# Analog_Breakout_-_Schematic.net
KiCad netlist of a schematic drawn in EAGLE
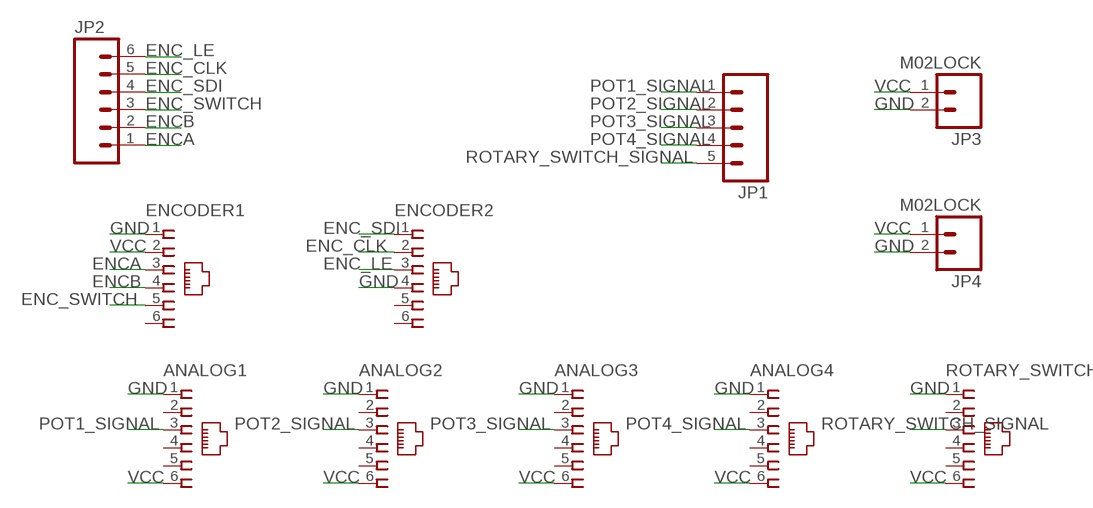
[diagram p0: schematic, sheet 1]

(export (version "E")
  (design (tool "Eeschema 10.0.6"))
  (components
    (comp (ref "ANALOG1")
      (value "555165-1")
      (footprint "eagle-import:555165-1")
      (libsource (lib "eagle-import") (part "555165-1"))
    )
    (comp (ref "ANALOG2")
      (value "555165-1")
      (footprint "eagle-import:555165-1")
      (libsource (lib "eagle-import") (part "555165-1"))
    )
    (comp (ref "ANALOG3")
      (value "555165-1")
      (footprint "eagle-import:555165-1")
      (libsource (lib "eagle-import") (part "555165-1"))
    )
    (comp (ref "ANALOG4")
      (value "555165-1")
      (footprint "eagle-import:555165-1")
      (libsource (lib "eagle-import") (part "555165-1"))
    )
    (comp (ref "ENCODER1")
      (value "555165-1")
      (footprint "eagle-import:555165-1")
      (libsource (lib "eagle-import") (part "555165-1"))
    )
    (comp (ref "ENCODER2")
      (value "555165-1")
      (footprint "eagle-import:555165-1")
      (libsource (lib "eagle-import") (part "555165-1"))
    )
    (comp (ref "JP1")
      (value "M05LOCK")
      (footprint "eagle-import:1X05_LOCK")
      (libsource (lib "eagle-import") (part "M05LOCK"))
    )
    (comp (ref "JP2")
      (value "M06LOCK")
      (footprint "eagle-import:1X06_LOCK")
      (libsource (lib "eagle-import") (part "M06LOCK"))
    )
    (comp (ref "JP3")
      (value "M02LOCK")
      (footprint "eagle-import:1X02_LOCK")
      (libsource (lib "eagle-import") (part "M02LOCK"))
    )
    (comp (ref "JP4")
      (value "M02LOCK")
      (footprint "eagle-import:1X02_LOCK")
      (libsource (lib "eagle-import") (part "M02LOCK"))
    )
    (comp (ref "ROTARY_SWITCH")
      (value "555165-1")
      (footprint "eagle-import:555165-1")
      (libsource (lib "eagle-import") (part "555165-1"))
    )
  )
  (nets
    (net (code "1") (name "/ENCA") (class "Default")
      (node (ref "ENCODER1") (pin "3") (pinfunction "3_3") (pintype "passive"))
      (node (ref "JP2") (pin "1") (pinfunction "1_1") (pintype "passive"))
    )
    (net (code "2") (name "/ENCB") (class "Default")
      (node (ref "ENCODER1") (pin "4") (pinfunction "4_4") (pintype "passive"))
      (node (ref "JP2") (pin "2") (pinfunction "2_2") (pintype "passive"))
    )
    (net (code "3") (name "/ENC_CLK") (class "Default")
      (node (ref "ENCODER2") (pin "2") (pinfunction "2_2") (pintype "passive"))
      (node (ref "JP2") (pin "5") (pinfunction "5_5") (pintype "passive"))
    )
    (net (code "4") (name "/ENC_LE") (class "Default")
      (node (ref "ENCODER2") (pin "3") (pinfunction "3_3") (pintype "passive"))
      (node (ref "JP2") (pin "6") (pinfunction "6_6") (pintype "passive"))
    )
    (net (code "5") (name "/ENC_SDI") (class "Default")
      (node (ref "ENCODER2") (pin "1") (pinfunction "1_1") (pintype "passive"))
      (node (ref "JP2") (pin "4") (pinfunction "4_4") (pintype "passive"))
    )
    (net (code "6") (name "/ENC_SWITCH") (class "Default")
      (node (ref "ENCODER1") (pin "5") (pinfunction "5_5") (pintype "passive"))
      (node (ref "JP2") (pin "3") (pinfunction "3_3") (pintype "passive"))
    )
    (net (code "7") (name "/GND") (class "Default")
      (node (ref "ANALOG1") (pin "1") (pinfunction "1_1") (pintype "passive"))
      (node (ref "ANALOG2") (pin "1") (pinfunction "1_1") (pintype "passive"))
      (node (ref "ANALOG3") (pin "1") (pinfunction "1_1") (pintype "passive"))
      (node (ref "ANALOG4") (pin "1") (pinfunction "1_1") (pintype "passive"))
      (node (ref "ENCODER1") (pin "1") (pinfunction "1_1") (pintype "passive"))
      (node (ref "ENCODER2") (pin "4") (pinfunction "4_4") (pintype "passive"))
      (node (ref "JP3") (pin "2") (pinfunction "2_2") (pintype "passive"))
      (node (ref "JP4") (pin "2") (pinfunction "2_2") (pintype "passive"))
      (node (ref "ROTARY_SWITCH") (pin "1") (pinfunction "1_1") (pintype "passive"))
    )
    (net (code "8") (name "/POT1_SIGNAL") (class "Default")
      (node (ref "ANALOG1") (pin "3") (pinfunction "3_3") (pintype "passive"))
      (node (ref "JP1") (pin "1") (pinfunction "1_1") (pintype "passive"))
    )
    (net (code "9") (name "/POT2_SIGNAL") (class "Default")
      (node (ref "ANALOG2") (pin "3") (pinfunction "3_3") (pintype "passive"))
      (node (ref "JP1") (pin "2") (pinfunction "2_2") (pintype "passive"))
    )
    (net (code "10") (name "/POT3_SIGNAL") (class "Default")
      (node (ref "ANALOG3") (pin "3") (pinfunction "3_3") (pintype "passive"))
      (node (ref "JP1") (pin "3") (pinfunction "3_3") (pintype "passive"))
    )
    (net (code "11") (name "/POT4_SIGNAL") (class "Default")
      (node (ref "ANALOG4") (pin "3") (pinfunction "3_3") (pintype "passive"))
      (node (ref "JP1") (pin "4") (pinfunction "4_4") (pintype "passive"))
    )
    (net (code "12") (name "/ROTARY_SWITCH_SIGNAL") (class "Default")
      (node (ref "JP1") (pin "5") (pinfunction "5_5") (pintype "passive"))
      (node (ref "ROTARY_SWITCH") (pin "3") (pinfunction "3_3") (pintype "passive"))
    )
    (net (code "13") (name "/VCC") (class "Default")
      (node (ref "ANALOG1") (pin "6") (pinfunction "6_6") (pintype "passive"))
      (node (ref "ANALOG2") (pin "6") (pinfunction "6_6") (pintype "passive"))
      (node (ref "ANALOG3") (pin "6") (pinfunction "6_6") (pintype "passive"))
      (node (ref "ANALOG4") (pin "6") (pinfunction "6_6") (pintype "passive"))
      (node (ref "ENCODER1") (pin "2") (pinfunction "2_2") (pintype "passive"))
      (node (ref "JP3") (pin "1") (pinfunction "1_1") (pintype "passive"))
      (node (ref "JP4") (pin "1") (pinfunction "1_1") (pintype "passive"))
      (node (ref "ROTARY_SWITCH") (pin "6") (pinfunction "6_6") (pintype "passive"))
    )
    (net (code "14") (name "unconnected-(ANALOG1-Pad2)") (class "Default")
      (node (ref "ANALOG1") (pin "2") (pinfunction "2_2") (pintype "passive"))
    )
    (net (code "15") (name "unconnected-(ANALOG1-Pad4)") (class "Default")
      (node (ref "ANALOG1") (pin "4") (pinfunction "4_4") (pintype "passive"))
    )
    (net (code "16") (name "unconnected-(ANALOG1-Pad5)") (class "Default")
      (node (ref "ANALOG1") (pin "5") (pinfunction "5_5") (pintype "passive"))
    )
    (net (code "17") (name "unconnected-(ANALOG2-Pad2)") (class "Default")
      (node (ref "ANALOG2") (pin "2") (pinfunction "2_2") (pintype "passive"))
    )
    (net (code "18") (name "unconnected-(ANALOG2-Pad4)") (class "Default")
      (node (ref "ANALOG2") (pin "4") (pinfunction "4_4") (pintype "passive"))
    )
    (net (code "19") (name "unconnected-(ANALOG2-Pad5)") (class "Default")
      (node (ref "ANALOG2") (pin "5") (pinfunction "5_5") (pintype "passive"))
    )
    (net (code "20") (name "unconnected-(ANALOG3-Pad2)") (class "Default")
      (node (ref "ANALOG3") (pin "2") (pinfunction "2_2") (pintype "passive"))
    )
    (net (code "21") (name "unconnected-(ANALOG3-Pad4)") (class "Default")
      (node (ref "ANALOG3") (pin "4") (pinfunction "4_4") (pintype "passive"))
    )
    (net (code "22") (name "unconnected-(ANALOG3-Pad5)") (class "Default")
      (node (ref "ANALOG3") (pin "5") (pinfunction "5_5") (pintype "passive"))
    )
    (net (code "23") (name "unconnected-(ANALOG4-Pad2)") (class "Default")
      (node (ref "ANALOG4") (pin "2") (pinfunction "2_2") (pintype "passive"))
    )
    (net (code "24") (name "unconnected-(ANALOG4-Pad4)") (class "Default")
      (node (ref "ANALOG4") (pin "4") (pinfunction "4_4") (pintype "passive"))
    )
    (net (code "25") (name "unconnected-(ANALOG4-Pad5)") (class "Default")
      (node (ref "ANALOG4") (pin "5") (pinfunction "5_5") (pintype "passive"))
    )
    (net (code "26") (name "unconnected-(ENCODER1-Pad6)") (class "Default")
      (node (ref "ENCODER1") (pin "6") (pinfunction "6_6") (pintype "passive"))
    )
    (net (code "27") (name "unconnected-(ENCODER2-Pad5)") (class "Default")
      (node (ref "ENCODER2") (pin "5") (pinfunction "5_5") (pintype "passive"))
    )
    (net (code "28") (name "unconnected-(ENCODER2-Pad6)") (class "Default")
      (node (ref "ENCODER2") (pin "6") (pinfunction "6_6") (pintype "passive"))
    )
    (net (code "29") (name "unconnected-(ROTARY_SWITCH-Pad2)") (class "Default")
      (node (ref "ROTARY_SWITCH") (pin "2") (pinfunction "2_2") (pintype "passive"))
    )
    (net (code "30") (name "unconnected-(ROTARY_SWITCH-Pad4)") (class "Default")
      (node (ref "ROTARY_SWITCH") (pin "4") (pinfunction "4_4") (pintype "passive"))
    )
    (net (code "31") (name "unconnected-(ROTARY_SWITCH-Pad5)") (class "Default")
      (node (ref "ROTARY_SWITCH") (pin "5") (pinfunction "5_5") (pintype "passive"))
    )
  )
)
